# DriverV3_0.net
KiCad netlist of a schematic drawn in Altium Designer
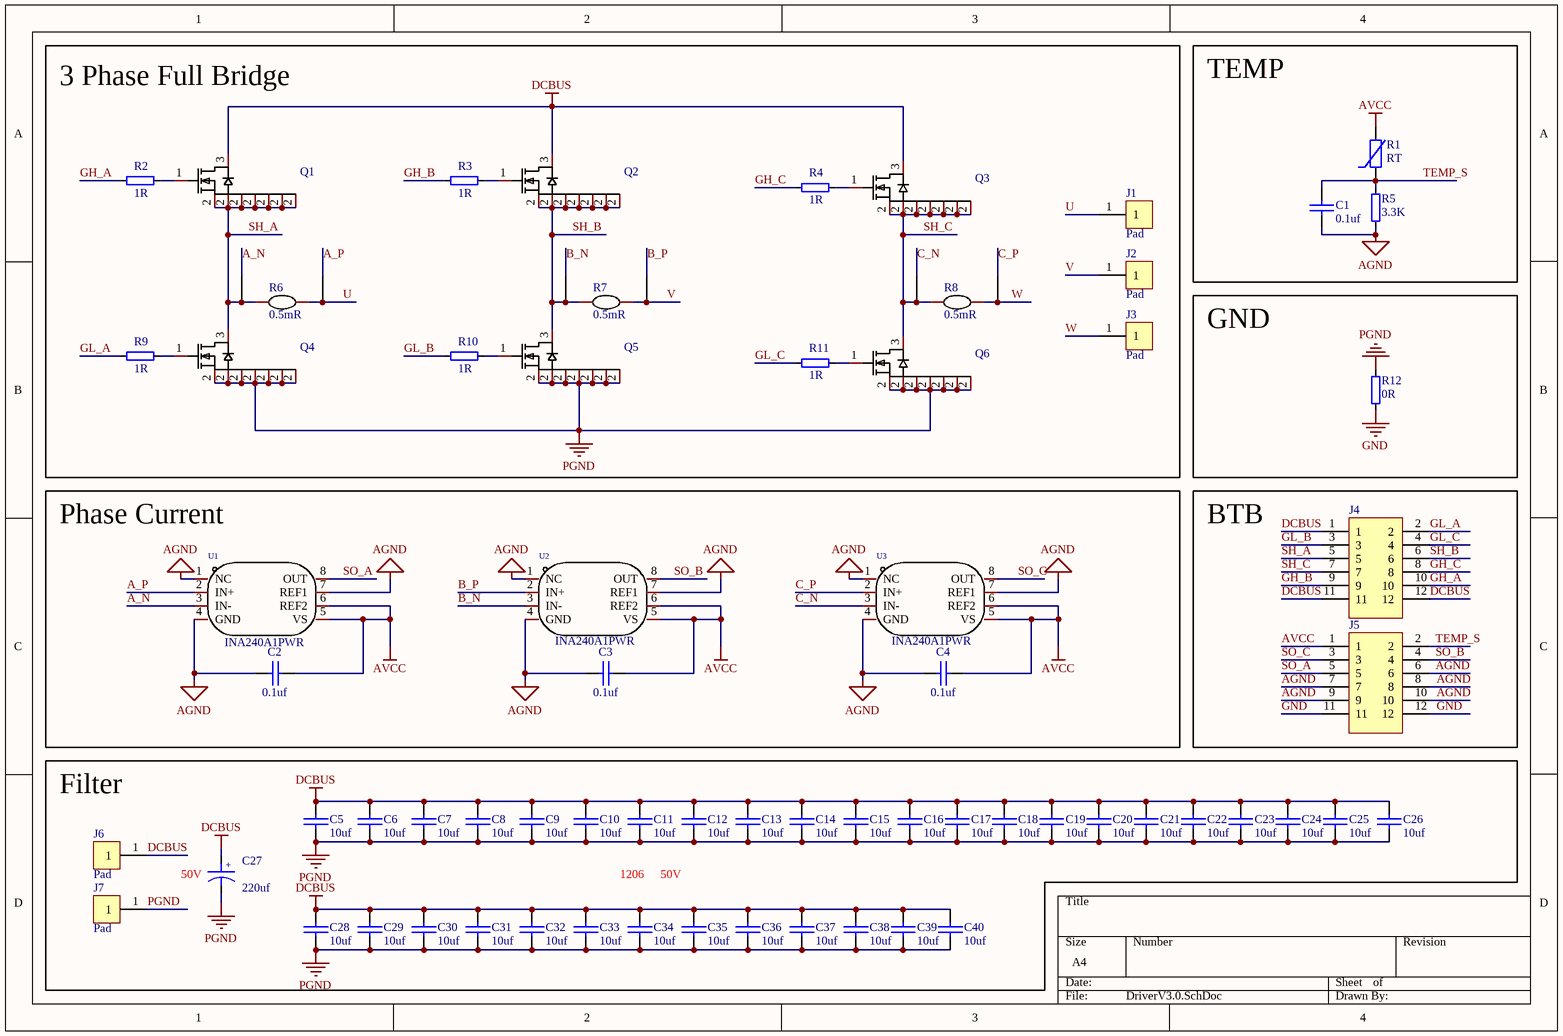
[diagram p0: DriverV3.0.SchDoc]

(export (version "E")
  (design (tool "Eeschema 10.0.6"))
  (components
    (comp (ref "C1")
      (value "0.1uf")
      (footprint "C0603_S")
      (description "贴片电容")
      (libsource (lib "Driver") (part "CAP"))
    )
    (comp (ref "C2")
      (value "0.1uf")
      (footprint "C0603_S")
      (description "贴片电容")
      (libsource (lib "Driver") (part "CAP"))
    )
    (comp (ref "C3")
      (value "0.1uf")
      (footprint "C0603_S")
      (description "贴片电容")
      (libsource (lib "Driver") (part "CAP"))
    )
    (comp (ref "C4")
      (value "0.1uf")
      (footprint "C0603_S")
      (description "贴片电容")
      (libsource (lib "Driver") (part "CAP"))
    )
    (comp (ref "C5")
      (value "10uf")
      (footprint "1206C")
      (description "贴片电容")
      (libsource (lib "Driver") (part "CAP"))
    )
    (comp (ref "C6")
      (value "10uf")
      (footprint "1206C")
      (description "贴片电容")
      (libsource (lib "Driver") (part "CAP"))
    )
    (comp (ref "C7")
      (value "10uf")
      (footprint "1206C")
      (description "贴片电容")
      (libsource (lib "Driver") (part "CAP"))
    )
    (comp (ref "C8")
      (value "10uf")
      (footprint "1206C")
      (description "贴片电容")
      (libsource (lib "Driver") (part "CAP"))
    )
    (comp (ref "C9")
      (value "10uf")
      (footprint "1206C")
      (description "贴片电容")
      (libsource (lib "Driver") (part "CAP"))
    )
    (comp (ref "C10")
      (value "10uf")
      (footprint "1206C")
      (description "贴片电容")
      (libsource (lib "Driver") (part "CAP"))
    )
    (comp (ref "C11")
      (value "10uf")
      (footprint "1206C")
      (description "贴片电容")
      (libsource (lib "Driver") (part "CAP"))
    )
    (comp (ref "C12")
      (value "10uf")
      (footprint "1206C")
      (description "贴片电容")
      (libsource (lib "Driver") (part "CAP"))
    )
    (comp (ref "C13")
      (value "10uf")
      (footprint "1206C")
      (description "贴片电容")
      (libsource (lib "Driver") (part "CAP"))
    )
    (comp (ref "C14")
      (value "10uf")
      (footprint "1206C")
      (description "贴片电容")
      (libsource (lib "Driver") (part "CAP"))
    )
    (comp (ref "C15")
      (value "10uf")
      (footprint "1206C")
      (description "贴片电容")
      (libsource (lib "Driver") (part "CAP"))
    )
    (comp (ref "C16")
      (value "10uf")
      (footprint "1206C")
      (description "贴片电容")
      (libsource (lib "Driver") (part "CAP"))
    )
    (comp (ref "C17")
      (value "10uf")
      (footprint "1206C")
      (description "贴片电容")
      (libsource (lib "Driver") (part "CAP"))
    )
    (comp (ref "C18")
      (value "10uf")
      (footprint "1206C")
      (description "贴片电容")
      (libsource (lib "Driver") (part "CAP"))
    )
    (comp (ref "C19")
      (value "10uf")
      (footprint "1206C")
      (description "贴片电容")
      (libsource (lib "Driver") (part "CAP"))
    )
    (comp (ref "C20")
      (value "10uf")
      (footprint "1206C")
      (description "贴片电容")
      (libsource (lib "Driver") (part "CAP"))
    )
    (comp (ref "C21")
      (value "10uf")
      (footprint "1206C")
      (description "贴片电容")
      (libsource (lib "Driver") (part "CAP"))
    )
    (comp (ref "C22")
      (value "10uf")
      (footprint "1206C")
      (description "贴片电容")
      (libsource (lib "Driver") (part "CAP"))
    )
    (comp (ref "C23")
      (value "10uf")
      (footprint "1206C")
      (description "贴片电容")
      (libsource (lib "Driver") (part "CAP"))
    )
    (comp (ref "C24")
      (value "10uf")
      (footprint "1206C")
      (description "贴片电容")
      (libsource (lib "Driver") (part "CAP"))
    )
    (comp (ref "C25")
      (value "10uf")
      (footprint "1206C")
      (description "贴片电容")
      (libsource (lib "Driver") (part "CAP"))
    )
    (comp (ref "C26")
      (value "10uf")
      (footprint "1206C")
      (description "贴片电容")
      (libsource (lib "Driver") (part "CAP"))
    )
    (comp (ref "C27")
      (value "220uf")
      (footprint "ELECTRO10-5-N")
      (description "极性电容")
      (libsource (lib "Driver") (part "CAP+"))
    )
    (comp (ref "C28")
      (value "10uf")
      (footprint "1206C")
      (description "贴片电容")
      (libsource (lib "Driver") (part "CAP"))
    )
    (comp (ref "C29")
      (value "10uf")
      (footprint "1206C")
      (description "贴片电容")
      (libsource (lib "Driver") (part "CAP"))
    )
    (comp (ref "C30")
      (value "10uf")
      (footprint "1206C")
      (description "贴片电容")
      (libsource (lib "Driver") (part "CAP"))
    )
    (comp (ref "C31")
      (value "10uf")
      (footprint "1206C")
      (description "贴片电容")
      (libsource (lib "Driver") (part "CAP"))
    )
    (comp (ref "C32")
      (value "10uf")
      (footprint "1206C")
      (description "贴片电容")
      (libsource (lib "Driver") (part "CAP"))
    )
    (comp (ref "C33")
      (value "10uf")
      (footprint "1206C")
      (description "贴片电容")
      (libsource (lib "Driver") (part "CAP"))
    )
    (comp (ref "C34")
      (value "10uf")
      (footprint "1206C")
      (description "贴片电容")
      (libsource (lib "Driver") (part "CAP"))
    )
    (comp (ref "C35")
      (value "10uf")
      (footprint "1206C")
      (description "贴片电容")
      (libsource (lib "Driver") (part "CAP"))
    )
    (comp (ref "C36")
      (value "10uf")
      (footprint "1206C")
      (description "贴片电容")
      (libsource (lib "Driver") (part "CAP"))
    )
    (comp (ref "C37")
      (value "10uf")
      (footprint "1206C")
      (description "贴片电容")
      (libsource (lib "Driver") (part "CAP"))
    )
    (comp (ref "C38")
      (value "10uf")
      (footprint "1206C")
      (description "贴片电容")
      (libsource (lib "Driver") (part "CAP"))
    )
    (comp (ref "C39")
      (value "10uf")
      (footprint "1206C")
      (description "贴片电容")
      (libsource (lib "Driver") (part "CAP"))
    )
    (comp (ref "C40")
      (value "10uf")
      (footprint "1206C")
      (description "贴片电容")
      (libsource (lib "Driver") (part "CAP"))
    )
    (comp (ref "J1")
      (value "Pad")
      (footprint "PAD_RECT")
      (description "焊盘")
      (libsource (lib "") (part "Pad_1"))
    )
    (comp (ref "J2")
      (value "Pad")
      (footprint "PAD_RECT")
      (description "焊盘")
      (libsource (lib "") (part "Pad_1"))
    )
    (comp (ref "J3")
      (value "Pad")
      (footprint "PAD_RECT")
      (description "焊盘")
      (libsource (lib "") (part "Pad_1"))
    )
    (comp (ref "J4")
      (value "BTB-2X6-M")
      (footprint "BTB-M-0.8mm-2x6P")
      (description "0.8间距2x6P公座")
      (libsource (lib "Driver") (part "BTB-2X6-M"))
    )
    (comp (ref "J5")
      (value "BTB-2X6-M")
      (footprint "BTB-M-0.8mm-2x6P")
      (description "0.8间距2x6P公座")
      (libsource (lib "Driver") (part "BTB-2X6-M"))
    )
    (comp (ref "J6")
      (value "Pad")
      (footprint "PAD_RECT")
      (description "焊盘")
      (libsource (lib "Driver") (part "Pad"))
    )
    (comp (ref "J7")
      (value "Pad")
      (footprint "PAD_RECT")
      (description "焊盘")
      (libsource (lib "Driver") (part "Pad"))
    )
    (comp (ref "NT1")
      (value "0.25mm")
      (footprint "Nettie10mil")
      (libsource (lib "Driver") (part "NetTie_10mil"))
    )
    (comp (ref "NT2")
      (value "0.25mm")
      (footprint "Nettie10mil")
      (libsource (lib "Driver") (part "NetTie_10mil"))
    )
    (comp (ref "NT3")
      (value "0.25mm")
      (footprint "Nettie10mil")
      (libsource (lib "Driver") (part "NetTie_10mil"))
    )
    (comp (ref "NT4")
      (value "0.25mm")
      (footprint "Nettie10mil")
      (libsource (lib "Driver") (part "NetTie_10mil"))
    )
    (comp (ref "NT5")
      (value "0.25mm")
      (footprint "Nettie10mil")
      (libsource (lib "Driver") (part "NetTie_10mil"))
    )
    (comp (ref "NT6")
      (value "0.25mm")
      (footprint "Nettie10mil")
      (libsource (lib "Driver") (part "NetTie_10mil"))
    )
    (comp (ref "Q1")
      (value "HYG006N04LS1TA")
      (footprint "TOLL")
      (description "N沟道增强型MOS 40V-600A")
      (fields (field (name "MANUFACTURER") "HUAYI(华羿微)"))
      (libsource (lib "Driver") (part "HYG006N04LS1TA"))
    )
    (comp (ref "Q2")
      (value "HYG006N04LS1TA")
      (footprint "TOLL")
      (description "N沟道增强型MOS 40V-600A")
      (fields (field (name "MANUFACTURER") "HUAYI(华羿微)"))
      (libsource (lib "Driver") (part "HYG006N04LS1TA"))
    )
    (comp (ref "Q3")
      (value "HYG006N04LS1TA")
      (footprint "TOLL")
      (description "N沟道增强型MOS 40V-600A")
      (fields (field (name "MANUFACTURER") "HUAYI(华羿微)"))
      (libsource (lib "Driver") (part "HYG006N04LS1TA"))
    )
    (comp (ref "Q4")
      (value "HYG006N04LS1TA")
      (footprint "TOLL")
      (description "N沟道增强型MOS 40V-600A")
      (fields (field (name "MANUFACTURER") "HUAYI(华羿微)"))
      (libsource (lib "Driver") (part "HYG006N04LS1TA"))
    )
    (comp (ref "Q5")
      (value "HYG006N04LS1TA")
      (footprint "TOLL")
      (description "N沟道增强型MOS 40V-600A")
      (fields (field (name "MANUFACTURER") "HUAYI(华羿微)"))
      (libsource (lib "Driver") (part "HYG006N04LS1TA"))
    )
    (comp (ref "Q6")
      (value "HYG006N04LS1TA")
      (footprint "TOLL")
      (description "N沟道增强型MOS 40V-600A")
      (fields (field (name "MANUFACTURER") "HUAYI(华羿微)"))
      (libsource (lib "Driver") (part "HYG006N04LS1TA"))
    )
    (comp (ref "R1")
      (value "RT")
      (footprint "R0603_S")
      (description "热敏电阻 NCP18XH103F03RB")
      (libsource (lib "Driver") (part "RT"))
    )
    (comp (ref "R2")
      (value "1R")
      (footprint "R0603_S")
      (description "贴片电阻")
      (libsource (lib "Driver") (part "RES"))
    )
    (comp (ref "R3")
      (value "1R")
      (footprint "R0603_S")
      (description "贴片电阻")
      (libsource (lib "Driver") (part "RES"))
    )
    (comp (ref "R4")
      (value "1R")
      (footprint "R0603_S")
      (description "贴片电阻")
      (libsource (lib "Driver") (part "RES"))
    )
    (comp (ref "R5")
      (value "3.3K")
      (footprint "R0603_S")
      (description "贴片电阻")
      (libsource (lib "Driver") (part "RES"))
    )
    (comp (ref "R6")
      (value "0.5mR")
      (footprint "3920R")
      (description "采样电阻")
      (fields (field (name "MANUFACTURER") "RESI(开步睿思）") (field (name "MANUFACTURER PART") "SEWF3920F1L00P9"))
      (libsource (lib "Driver") (part "HoLRS3920"))
    )
    (comp (ref "R7")
      (value "0.5mR")
      (footprint "3920R")
      (description "采样电阻")
      (fields (field (name "MANUFACTURER") "RESI(开步睿思）") (field (name "MANUFACTURER PART") "SEWF3920F1L00P9"))
      (libsource (lib "Driver") (part "HoLRS3920"))
    )
    (comp (ref "R8")
      (value "0.5mR")
      (footprint "3920R")
      (description "采样电阻")
      (fields (field (name "MANUFACTURER") "RESI(开步睿思）") (field (name "MANUFACTURER PART") "SEWF3920F1L00P9"))
      (libsource (lib "Driver") (part "HoLRS3920"))
    )
    (comp (ref "R9")
      (value "1R")
      (footprint "R0603_S")
      (description "贴片电阻")
      (libsource (lib "Driver") (part "RES"))
    )
    (comp (ref "R10")
      (value "1R")
      (footprint "R0603_S")
      (description "贴片电阻")
      (libsource (lib "Driver") (part "RES"))
    )
    (comp (ref "R11")
      (value "1R")
      (footprint "R0603_S")
      (description "贴片电阻")
      (libsource (lib "Driver") (part "RES"))
    )
    (comp (ref "R12")
      (value "0R")
      (footprint "R0603_S")
      (description "贴片电阻")
      (libsource (lib "Driver") (part "RES"))
    )
    (comp (ref "U1")
      (value "INA240A1PWR")
      (footprint "TSSOP-8")
      (fields (field (name "MANUFACTURER") "TI(德州仪器)") (field (name "NAME") "INA240A1PWR"))
      (libsource (lib "Driver") (part "INA240A1PWR"))
    )
    (comp (ref "U2")
      (value "INA240A1PWR")
      (footprint "TSSOP-8")
      (fields (field (name "MANUFACTURER") "TI(德州仪器)") (field (name "NAME") "INA240A1PWR"))
      (libsource (lib "Driver") (part "INA240A1PWR"))
    )
    (comp (ref "U3")
      (value "INA240A1PWR")
      (footprint "TSSOP-8")
      (fields (field (name "MANUFACTURER") "TI(德州仪器)") (field (name "NAME") "INA240A1PWR"))
      (libsource (lib "Driver") (part "INA240A1PWR"))
    )
  )
  (nets
    (net (code "1") (name "/A_N") (class "Default")
      (node (ref "NT1") (pin "2") (pinfunction "2_2") (pintype "passive"))
      (node (ref "U1") (pin "3") (pinfunction "IN-_3") (pintype "passive"))
    )
    (net (code "2") (name "/A_P") (class "Default")
      (node (ref "NT2") (pin "2") (pinfunction "2_2") (pintype "passive"))
      (node (ref "U1") (pin "2") (pinfunction "IN+_2") (pintype "passive"))
    )
    (net (code "3") (name "/B_N") (class "Default")
      (node (ref "NT3") (pin "2") (pinfunction "2_2") (pintype "passive"))
      (node (ref "U2") (pin "3") (pinfunction "IN-_3") (pintype "passive"))
    )
    (net (code "4") (name "/B_P") (class "Default")
      (node (ref "NT4") (pin "2") (pinfunction "2_2") (pintype "passive"))
      (node (ref "U2") (pin "2") (pinfunction "IN+_2") (pintype "passive"))
    )
    (net (code "5") (name "/C_N") (class "Default")
      (node (ref "NT5") (pin "2") (pinfunction "2_2") (pintype "passive"))
      (node (ref "U3") (pin "3") (pinfunction "IN-_3") (pintype "passive"))
    )
    (net (code "6") (name "/C_P") (class "Default")
      (node (ref "NT6") (pin "2") (pinfunction "2_2") (pintype "passive"))
      (node (ref "U3") (pin "2") (pinfunction "IN+_2") (pintype "passive"))
    )
    (net (code "7") (name "/GH_A") (class "Default")
      (node (ref "J4") (pin "10") (pinfunction "10_10") (pintype "passive"))
      (node (ref "R2") (pin "1") (pinfunction "1_1") (pintype "passive"))
    )
    (net (code "8") (name "/GH_B") (class "Default")
      (node (ref "J4") (pin "9") (pinfunction "9_9") (pintype "passive"))
      (node (ref "R3") (pin "1") (pinfunction "1_1") (pintype "passive"))
    )
    (net (code "9") (name "/GH_C") (class "Default")
      (node (ref "J4") (pin "8") (pinfunction "8_8") (pintype "passive"))
      (node (ref "R4") (pin "1") (pinfunction "1_1") (pintype "passive"))
    )
    (net (code "10") (name "/GL_A") (class "Default")
      (node (ref "J4") (pin "2") (pinfunction "2_2") (pintype "passive"))
      (node (ref "R9") (pin "1") (pinfunction "1_1") (pintype "passive"))
    )
    (net (code "11") (name "/GL_B") (class "Default")
      (node (ref "J4") (pin "3") (pinfunction "3_3") (pintype "passive"))
      (node (ref "R10") (pin "1") (pinfunction "1_1") (pintype "passive"))
    )
    (net (code "12") (name "/GL_C") (class "Default")
      (node (ref "J4") (pin "4") (pinfunction "4_4") (pintype "passive"))
      (node (ref "R11") (pin "1") (pinfunction "1_1") (pintype "passive"))
    )
    (net (code "13") (name "/SH_A") (class "Default")
      (node (ref "J4") (pin "5") (pinfunction "5_5") (pintype "passive"))
      (node (ref "NT1") (pin "1") (pintype "passive"))
      (node (ref "Q1") (pin "2") (pinfunction "S_2") (pintype "passive"))
      (node (ref "Q4") (pin "3") (pinfunction "D_3") (pintype "passive"))
      (node (ref "R6") (pin "1") (pinfunction "1_1") (pintype "passive"))
    )
    (net (code "14") (name "/SH_B") (class "Default")
      (node (ref "J4") (pin "6") (pinfunction "6_6") (pintype "passive"))
      (node (ref "NT3") (pin "1") (pintype "passive"))
      (node (ref "Q2") (pin "2") (pinfunction "S_2") (pintype "passive"))
      (node (ref "Q5") (pin "3") (pinfunction "D_3") (pintype "passive"))
      (node (ref "R7") (pin "1") (pinfunction "1_1") (pintype "passive"))
    )
    (net (code "15") (name "/SH_C") (class "Default")
      (node (ref "J4") (pin "7") (pinfunction "7_7") (pintype "passive"))
      (node (ref "NT5") (pin "1") (pintype "passive"))
      (node (ref "Q3") (pin "2") (pinfunction "S_2") (pintype "passive"))
      (node (ref "Q6") (pin "3") (pinfunction "D_3") (pintype "passive"))
      (node (ref "R8") (pin "1") (pinfunction "1_1") (pintype "passive"))
    )
    (net (code "16") (name "/SO_A") (class "Default")
      (node (ref "J5") (pin "5") (pinfunction "5_5") (pintype "passive"))
      (node (ref "U1") (pin "8") (pinfunction "OUT_8") (pintype "passive"))
    )
    (net (code "17") (name "/SO_B") (class "Default")
      (node (ref "J5") (pin "4") (pinfunction "4_4") (pintype "passive"))
      (node (ref "U2") (pin "8") (pinfunction "OUT_8") (pintype "passive"))
    )
    (net (code "18") (name "/SO_C") (class "Default")
      (node (ref "J5") (pin "3") (pinfunction "3_3") (pintype "passive"))
      (node (ref "U3") (pin "8") (pinfunction "OUT_8") (pintype "passive"))
    )
    (net (code "19") (name "/TEMP_S") (class "Default")
      (node (ref "C1") (pin "1") (pinfunction "1_1") (pintype "passive"))
      (node (ref "J5") (pin "2") (pinfunction "2_2") (pintype "passive"))
      (node (ref "R1") (pin "1") (pinfunction "1_1") (pintype "passive"))
      (node (ref "R5") (pin "2") (pinfunction "2_2") (pintype "passive"))
    )
    (net (code "20") (name "/U") (class "Default")
      (node (ref "J1") (pin "1") (pinfunction "1_1") (pintype "passive"))
      (node (ref "NT2") (pin "1") (pintype "passive"))
      (node (ref "R6") (pin "2") (pinfunction "2_2") (pintype "passive"))
    )
    (net (code "21") (name "/V") (class "Default")
      (node (ref "J2") (pin "1") (pinfunction "1_1") (pintype "passive"))
      (node (ref "NT4") (pin "1") (pintype "passive"))
      (node (ref "R7") (pin "2") (pinfunction "2_2") (pintype "passive"))
    )
    (net (code "22") (name "/W") (class "Default")
      (node (ref "J3") (pin "1") (pinfunction "1_1") (pintype "passive"))
      (node (ref "NT6") (pin "1") (pintype "passive"))
      (node (ref "R8") (pin "2") (pinfunction "2_2") (pintype "passive"))
    )
    (net (code "23") (name "AGND") (class "Default")
      (node (ref "C1") (pin "2") (pinfunction "2_2") (pintype "passive"))
      (node (ref "C2") (pin "1") (pinfunction "1_1") (pintype "passive"))
      (node (ref "C3") (pin "1") (pinfunction "1_1") (pintype "passive"))
      (node (ref "C4") (pin "1") (pinfunction "1_1") (pintype "passive"))
      (node (ref "J5") (pin "10") (pinfunction "10_10") (pintype "passive"))
      (node (ref "J5") (pin "6") (pinfunction "6_6") (pintype "passive"))
      (node (ref "J5") (pin "7") (pinfunction "7_7") (pintype "passive"))
      (node (ref "J5") (pin "8") (pinfunction "8_8") (pintype "passive"))
      (node (ref "J5") (pin "9") (pinfunction "9_9") (pintype "passive"))
      (node (ref "R5") (pin "1") (pinfunction "1_1") (pintype "passive"))
      (node (ref "U1") (pin "1") (pinfunction "NC_1") (pintype "passive"))
      (node (ref "U1") (pin "4") (pinfunction "GND_4") (pintype "passive"))
      (node (ref "U1") (pin "7") (pinfunction "REF1_7") (pintype "passive"))
      (node (ref "U2") (pin "1") (pinfunction "NC_1") (pintype "passive"))
      (node (ref "U2") (pin "4") (pinfunction "GND_4") (pintype "passive"))
      (node (ref "U2") (pin "7") (pinfunction "REF1_7") (pintype "passive"))
      (node (ref "U3") (pin "1") (pinfunction "NC_1") (pintype "passive"))
      (node (ref "U3") (pin "4") (pinfunction "GND_4") (pintype "passive"))
      (node (ref "U3") (pin "7") (pinfunction "REF1_7") (pintype "passive"))
    )
    (net (code "24") (name "AVCC") (class "Default")
      (node (ref "C2") (pin "2") (pinfunction "2_2") (pintype "passive"))
      (node (ref "C3") (pin "2") (pinfunction "2_2") (pintype "passive"))
      (node (ref "C4") (pin "2") (pinfunction "2_2") (pintype "passive"))
      (node (ref "J5") (pin "1") (pinfunction "1_1") (pintype "passive"))
      (node (ref "R1") (pin "2") (pinfunction "2_2") (pintype "passive"))
      (node (ref "U1") (pin "5") (pinfunction "VS_5") (pintype "passive"))
      (node (ref "U1") (pin "6") (pinfunction "REF2_6") (pintype "passive"))
      (node (ref "U2") (pin "5") (pinfunction "VS_5") (pintype "passive"))
      (node (ref "U2") (pin "6") (pinfunction "REF2_6") (pintype "passive"))
      (node (ref "U3") (pin "5") (pinfunction "VS_5") (pintype "passive"))
      (node (ref "U3") (pin "6") (pinfunction "REF2_6") (pintype "passive"))
    )
    (net (code "25") (name "DCBUS") (class "Default")
      (node (ref "C10") (pin "1") (pinfunction "1_1") (pintype "passive"))
      (node (ref "C11") (pin "1") (pinfunction "1_1") (pintype "passive"))
      (node (ref "C12") (pin "1") (pinfunction "1_1") (pintype "passive"))
      (node (ref "C13") (pin "1") (pinfunction "1_1") (pintype "passive"))
      (node (ref "C14") (pin "1") (pinfunction "1_1") (pintype "passive"))
      (node (ref "C15") (pin "1") (pinfunction "1_1") (pintype "passive"))
      (node (ref "C16") (pin "1") (pinfunction "1_1") (pintype "passive"))
      (node (ref "C17") (pin "1") (pinfunction "1_1") (pintype "passive"))
      (node (ref "C18") (pin "1") (pinfunction "1_1") (pintype "passive"))
      (node (ref "C19") (pin "1") (pinfunction "1_1") (pintype "passive"))
      (node (ref "C20") (pin "1") (pinfunction "1_1") (pintype "passive"))
      (node (ref "C21") (pin "1") (pinfunction "1_1") (pintype "passive"))
      (node (ref "C22") (pin "1") (pinfunction "1_1") (pintype "passive"))
      (node (ref "C23") (pin "1") (pinfunction "1_1") (pintype "passive"))
      (node (ref "C24") (pin "1") (pinfunction "1_1") (pintype "passive"))
      (node (ref "C25") (pin "1") (pinfunction "1_1") (pintype "passive"))
      (node (ref "C26") (pin "1") (pinfunction "1_1") (pintype "passive"))
      (node (ref "C27") (pin "1") (pinfunction "1_1") (pintype "passive"))
      (node (ref "C28") (pin "1") (pinfunction "1_1") (pintype "passive"))
      (node (ref "C29") (pin "1") (pinfunction "1_1") (pintype "passive"))
      (node (ref "C30") (pin "1") (pinfunction "1_1") (pintype "passive"))
      (node (ref "C31") (pin "1") (pinfunction "1_1") (pintype "passive"))
      (node (ref "C32") (pin "1") (pinfunction "1_1") (pintype "passive"))
      (node (ref "C33") (pin "1") (pinfunction "1_1") (pintype "passive"))
      (node (ref "C34") (pin "1") (pinfunction "1_1") (pintype "passive"))
      (node (ref "C35") (pin "1") (pinfunction "1_1") (pintype "passive"))
      (node (ref "C36") (pin "1") (pinfunction "1_1") (pintype "passive"))
      (node (ref "C37") (pin "1") (pinfunction "1_1") (pintype "passive"))
      (node (ref "C38") (pin "1") (pinfunction "1_1") (pintype "passive"))
      (node (ref "C39") (pin "1") (pinfunction "1_1") (pintype "passive"))
      (node (ref "C40") (pin "1") (pinfunction "1_1") (pintype "passive"))
      (node (ref "C5") (pin "1") (pinfunction "1_1") (pintype "passive"))
      (node (ref "C6") (pin "1") (pinfunction "1_1") (pintype "passive"))
      (node (ref "C7") (pin "1") (pinfunction "1_1") (pintype "passive"))
      (node (ref "C8") (pin "1") (pinfunction "1_1") (pintype "passive"))
      (node (ref "C9") (pin "1") (pinfunction "1_1") (pintype "passive"))
      (node (ref "J4") (pin "1") (pinfunction "1_1") (pintype "passive"))
      (node (ref "J4") (pin "11") (pinfunction "11_11") (pintype "passive"))
      (node (ref "J4") (pin "12") (pinfunction "12_12") (pintype "passive"))
      (node (ref "J6") (pin "1") (pinfunction "1_1") (pintype "passive"))
      (node (ref "Q1") (pin "3") (pinfunction "D_3") (pintype "passive"))
      (node (ref "Q2") (pin "3") (pinfunction "D_3") (pintype "passive"))
      (node (ref "Q3") (pin "3") (pinfunction "D_3") (pintype "passive"))
    )
    (net (code "26") (name "GND") (class "Default")
      (node (ref "J5") (pin "11") (pinfunction "11_11") (pintype "passive"))
      (node (ref "J5") (pin "12") (pinfunction "12_12") (pintype "passive"))
      (node (ref "R12") (pin "1") (pinfunction "1_1") (pintype "passive"))
    )
    (net (code "27") (name "Net-(Q1-G)") (class "Default")
      (node (ref "Q1") (pin "1") (pinfunction "G_1") (pintype "passive"))
      (node (ref "R2") (pin "2") (pinfunction "2_2") (pintype "passive"))
    )
    (net (code "28") (name "Net-(Q2-G)") (class "Default")
      (node (ref "Q2") (pin "1") (pinfunction "G_1") (pintype "passive"))
      (node (ref "R3") (pin "2") (pinfunction "2_2") (pintype "passive"))
    )
    (net (code "29") (name "Net-(Q3-G)") (class "Default")
      (node (ref "Q3") (pin "1") (pinfunction "G_1") (pintype "passive"))
      (node (ref "R4") (pin "2") (pinfunction "2_2") (pintype "passive"))
    )
    (net (code "30") (name "Net-(Q4-G)") (class "Default")
      (node (ref "Q4") (pin "1") (pinfunction "G_1") (pintype "passive"))
      (node (ref "R9") (pin "2") (pinfunction "2_2") (pintype "passive"))
    )
    (net (code "31") (name "Net-(Q5-G)") (class "Default")
      (node (ref "Q5") (pin "1") (pinfunction "G_1") (pintype "passive"))
      (node (ref "R10") (pin "2") (pinfunction "2_2") (pintype "passive"))
    )
    (net (code "32") (name "Net-(Q6-G)") (class "Default")
      (node (ref "Q6") (pin "1") (pinfunction "G_1") (pintype "passive"))
      (node (ref "R11") (pin "2") (pinfunction "2_2") (pintype "passive"))
    )
    (net (code "33") (name "PGND") (class "Default")
      (node (ref "C10") (pin "2") (pinfunction "2_2") (pintype "passive"))
      (node (ref "C11") (pin "2") (pinfunction "2_2") (pintype "passive"))
      (node (ref "C12") (pin "2") (pinfunction "2_2") (pintype "passive"))
      (node (ref "C13") (pin "2") (pinfunction "2_2") (pintype "passive"))
      (node (ref "C14") (pin "2") (pinfunction "2_2") (pintype "passive"))
      (node (ref "C15") (pin "2") (pinfunction "2_2") (pintype "passive"))
      (node (ref "C16") (pin "2") (pinfunction "2_2") (pintype "passive"))
      (node (ref "C17") (pin "2") (pinfunction "2_2") (pintype "passive"))
      (node (ref "C18") (pin "2") (pinfunction "2_2") (pintype "passive"))
      (node (ref "C19") (pin "2") (pinfunction "2_2") (pintype "passive"))
      (node (ref "C20") (pin "2") (pinfunction "2_2") (pintype "passive"))
      (node (ref "C21") (pin "2") (pinfunction "2_2") (pintype "passive"))
      (node (ref "C22") (pin "2") (pinfunction "2_2") (pintype "passive"))
      (node (ref "C23") (pin "2") (pinfunction "2_2") (pintype "passive"))
      (node (ref "C24") (pin "2") (pinfunction "2_2") (pintype "passive"))
      (node (ref "C25") (pin "2") (pinfunction "2_2") (pintype "passive"))
      (node (ref "C26") (pin "2") (pinfunction "2_2") (pintype "passive"))
      (node (ref "C27") (pin "2") (pinfunction "2_2") (pintype "passive"))
      (node (ref "C28") (pin "2") (pinfunction "2_2") (pintype "passive"))
      (node (ref "C29") (pin "2") (pinfunction "2_2") (pintype "passive"))
      (node (ref "C30") (pin "2") (pinfunction "2_2") (pintype "passive"))
      (node (ref "C31") (pin "2") (pinfunction "2_2") (pintype "passive"))
      (node (ref "C32") (pin "2") (pinfunction "2_2") (pintype "passive"))
      (node (ref "C33") (pin "2") (pinfunction "2_2") (pintype "passive"))
      (node (ref "C34") (pin "2") (pinfunction "2_2") (pintype "passive"))
      (node (ref "C35") (pin "2") (pinfunction "2_2") (pintype "passive"))
      (node (ref "C36") (pin "2") (pinfunction "2_2") (pintype "passive"))
      (node (ref "C37") (pin "2") (pinfunction "2_2") (pintype "passive"))
      (node (ref "C38") (pin "2") (pinfunction "2_2") (pintype "passive"))
      (node (ref "C39") (pin "2") (pinfunction "2_2") (pintype "passive"))
      (node (ref "C40") (pin "2") (pinfunction "2_2") (pintype "passive"))
      (node (ref "C5") (pin "2") (pinfunction "2_2") (pintype "passive"))
      (node (ref "C6") (pin "2") (pinfunction "2_2") (pintype "passive"))
      (node (ref "C7") (pin "2") (pinfunction "2_2") (pintype "passive"))
      (node (ref "C8") (pin "2") (pinfunction "2_2") (pintype "passive"))
      (node (ref "C9") (pin "2") (pinfunction "2_2") (pintype "passive"))
      (node (ref "J7") (pin "1") (pinfunction "1_1") (pintype "passive"))
      (node (ref "Q4") (pin "2") (pinfunction "S_2") (pintype "passive"))
      (node (ref "Q5") (pin "2") (pinfunction "S_2") (pintype "passive"))
      (node (ref "Q6") (pin "2") (pinfunction "S_2") (pintype "passive"))
      (node (ref "R12") (pin "2") (pinfunction "2_2") (pintype "passive"))
    )
  )
)
